# SCH1.net
KiCad netlist of a schematic drawn in Altium Designer
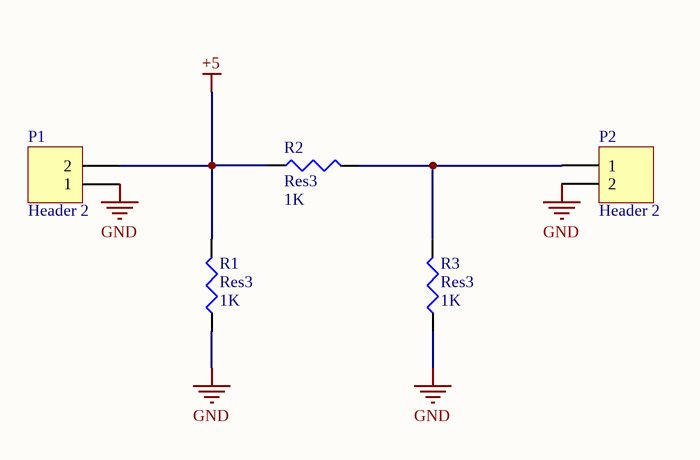
[diagram p0: SCH1.SchDoc]

(export (version "E")
  (design (tool "Eeschema 10.0.6"))
  (components
    (comp (ref "P1")
      (value "Header 2")
      (footprint "HDR1X2")
      (description "Header, 2-Pin")
      (fields (field (name "PUBLISHER") "Altium Limited"))
      (libsource (lib "") (part "Header 2_1"))
    )
    (comp (ref "P2")
      (value "Header 2")
      (footprint "HDR1X2")
      (description "Header, 2-Pin")
      (fields (field (name "PUBLISHER") "Altium Limited"))
      (libsource (lib "Miscellaneous Connectors") (part "Header 2"))
    )
    (comp (ref "R1")
      (value "Res3")
      (footprint "J1-0603")
      (description "Resistor")
      (fields (field (name "ALTIUM_VALUE") "1K") (field (name "PUBLISHER") "Altium Limited"))
      (libsource (lib "Miscellaneous Devices") (part "Res3"))
    )
    (comp (ref "R2")
      (value "Res3")
      (footprint "J1-0603")
      (description "Resistor")
      (fields (field (name "ALTIUM_VALUE") "1K") (field (name "PUBLISHER") "Altium Limited"))
      (libsource (lib "Miscellaneous Devices") (part "Res3"))
    )
    (comp (ref "R3")
      (value "Res3")
      (footprint "J1-0603")
      (description "Resistor")
      (fields (field (name "ALTIUM_VALUE") "1K") (field (name "PUBLISHER") "Altium Limited"))
      (libsource (lib "Miscellaneous Devices") (part "Res3"))
    )
  )
  (nets
    (net (code "1") (name "+5") (class "Default")
      (node (ref "P1") (pin "2") (pinfunction "2_2") (pintype "passive"))
      (node (ref "R1") (pin "2") (pinfunction "2_2") (pintype "passive"))
      (node (ref "R2") (pin "1") (pinfunction "1_1") (pintype "passive"))
    )
    (net (code "2") (name "GND") (class "Default")
      (node (ref "P1") (pin "1") (pinfunction "1_1") (pintype "passive"))
      (node (ref "P2") (pin "2") (pinfunction "2_2") (pintype "passive"))
      (node (ref "R1") (pin "1") (pinfunction "1_1") (pintype "passive"))
      (node (ref "R3") (pin "1") (pinfunction "1_1") (pintype "passive"))
    )
    (net (code "3") (name "Net-(P2-Pad1)") (class "Default")
      (node (ref "P2") (pin "1") (pinfunction "1_1") (pintype "passive"))
      (node (ref "R2") (pin "2") (pinfunction "2_2") (pintype "passive"))
      (node (ref "R3") (pin "2") (pinfunction "2_2") (pintype "passive"))
    )
  )
)
